# Connector-Section.net
KiCad netlist of a schematic drawn in Altium Designer
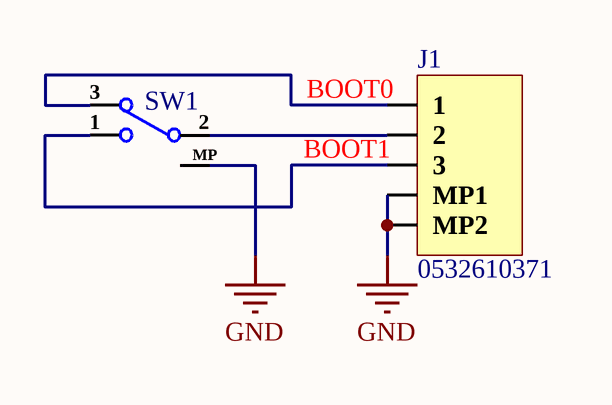
[diagram p0: Connector-Section.SchDoc]

(export (version "E")
  (design (tool "Eeschema 10.0.6"))
  (components
    (comp (ref "J1")
      (value "0532610371")
      (footprint "0532610371")
      (description "CONN HEADER SMD R/A 3POS 1.25MM")
      (fields (field (name "MANUFACTURER") "Molex") (field (name "MANUFACTURER PART NUMBER") "53261-0371"))
      (libsource (lib "Cole_Benson") (part "0532610371"))
    )
    (comp (ref "SW1")
      (value "PCM12SMTR")
      (footprint "PCM12SMTR_")
      (description "SWITCH SLIDE SPDT 300MA 6V")
      (fields (field (name "MANUFACTURER") "ITT C&K"))
      (libsource (lib "Cole_Benson") (part "PCM12SMTR"))
    )
  )
  (nets
    (net (code "1") (name "GND") (class "Default")
      (node (ref "J1") (pin "MP1") (pinfunction "MP1_MP1") (pintype "passive"))
      (node (ref "J1") (pin "MP2") (pinfunction "MP2_MP2") (pintype "passive"))
      (node (ref "SW1") (pin "MP") (pintype "passive"))
    )
    (net (code "2") (name "Net-(J1-Pad1)") (class "Default")
      (node (ref "J1") (pin "1") (pinfunction "1_1") (pintype "passive"))
      (node (ref "SW1") (pin "3") (pinfunction "3_3") (pintype "passive"))
    )
    (net (code "3") (name "Net-(J1-Pad2)") (class "Default")
      (node (ref "J1") (pin "2") (pinfunction "2_2") (pintype "passive"))
      (node (ref "SW1") (pin "2") (pinfunction "2_2") (pintype "passive"))
    )
    (net (code "4") (name "Net-(J1-Pad3)") (class "Default")
      (node (ref "J1") (pin "3") (pinfunction "3_3") (pintype "passive"))
      (node (ref "SW1") (pin "1") (pinfunction "1_1") (pintype "passive"))
    )
  )
)
